# ir2104_V2_1.net
KiCad netlist of a schematic drawn in EasyEDA Pro
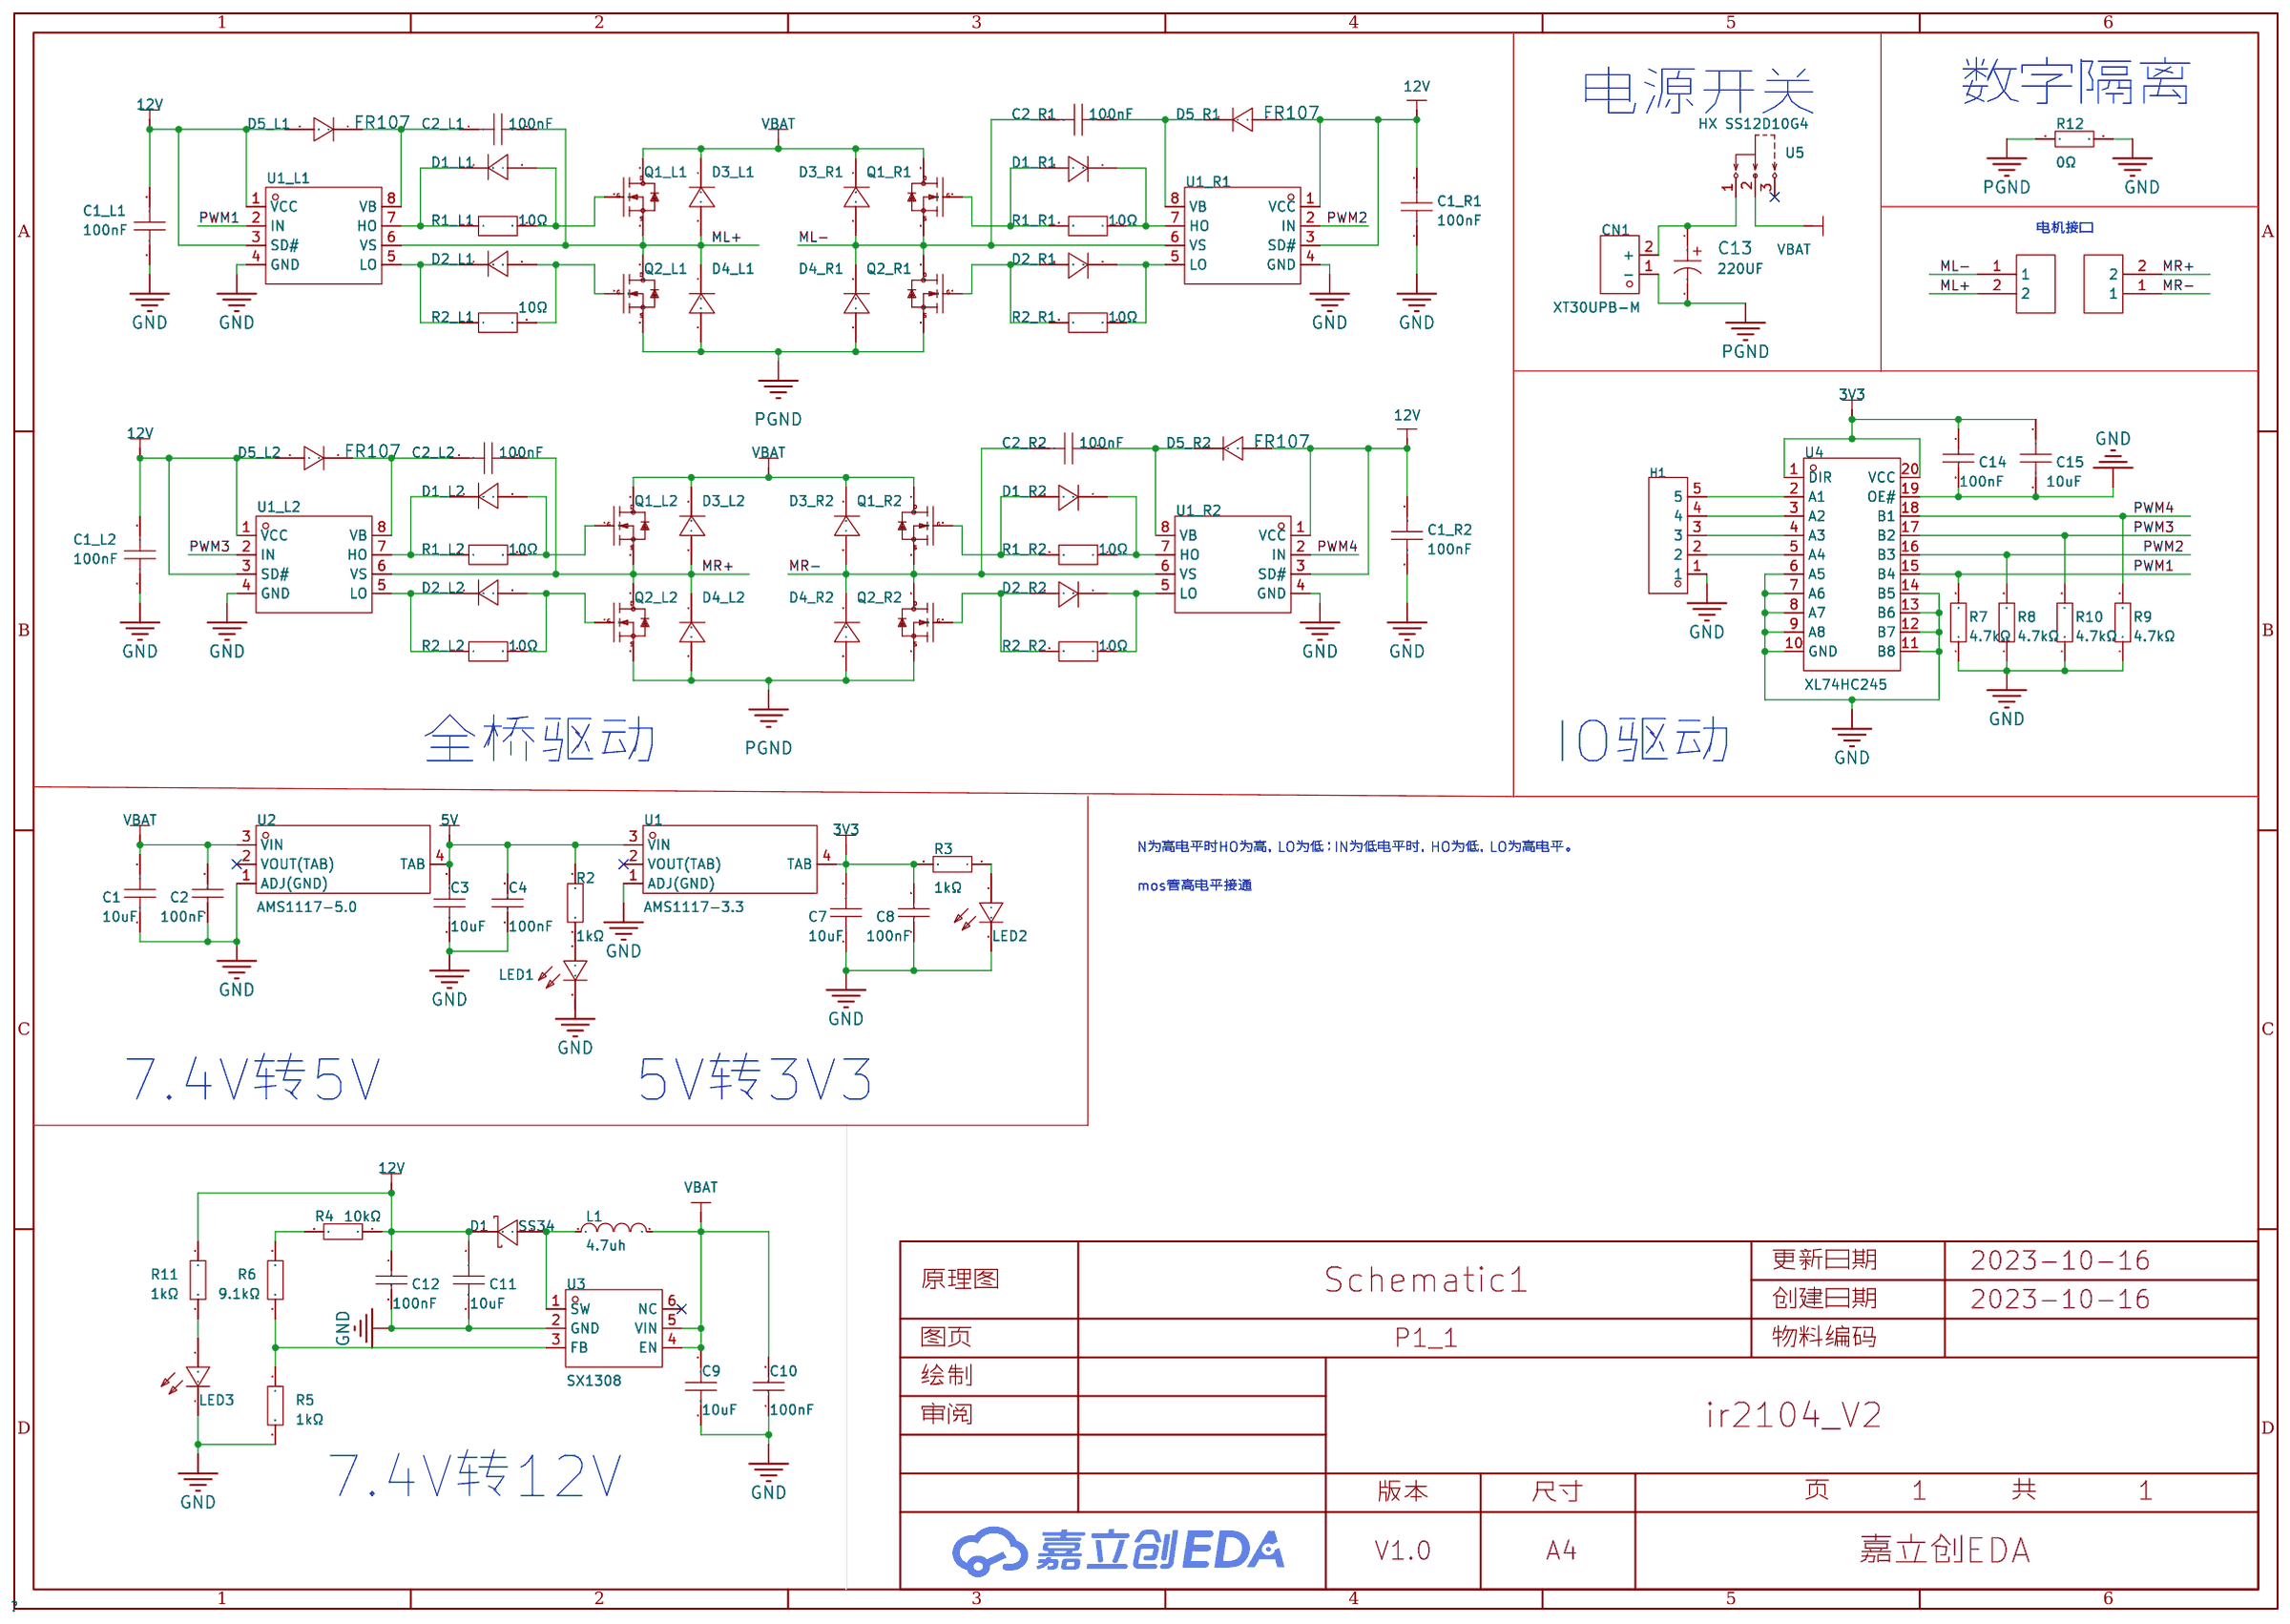
[diagram p0: schematic sheet]

(export (version "E")
  (design (tool "Eeschema 10.0.6"))
  (components
    (comp (ref "C1")
      (value "10uF")
      (footprint "easyedapro:C0603")
      (description "容值:10uF;精度:±20%;额定电压:25V;材质(温度系数):X5R;")
      (fields
        (field (name "Manufacturer Part") "CL10A106MA8NRNC")
        (field (name "Manufacturer") "SAMSUNG(三星)")
      )
      (libsource (lib "easyedapro") (part "CL10A106MA8NRNC"))
    )
    (comp (ref "C1_L1")
      (value "100nF")
      (footprint "easyedapro:C0603")
      (description "容值:100nF;精度:±10%;额定电压:50V;材质(温度系数):X7R;")
      (fields
        (field (name "Manufacturer Part") "CL10B104KB8NNNC")
        (field (name "Manufacturer") "SAMSUNG(三星)")
      )
      (libsource (lib "easyedapro") (part "CL10B104KB8NNNC"))
    )
    (comp (ref "C1_L2")
      (value "100nF")
      (footprint "easyedapro:C0603")
      (description "容值:100nF;精度:±10%;额定电压:50V;材质(温度系数):X7R;")
      (fields
        (field (name "Manufacturer Part") "CL10B104KB8NNNC")
        (field (name "Manufacturer") "SAMSUNG(三星)")
      )
      (libsource (lib "easyedapro") (part "CL10B104KB8NNNC"))
    )
    (comp (ref "C1_R1")
      (value "100nF")
      (footprint "easyedapro:C0603")
      (description "容值:100nF;精度:±10%;额定电压:50V;材质(温度系数):X7R;")
      (fields
        (field (name "Manufacturer Part") "CL10B104KB8NNNC")
        (field (name "Manufacturer") "SAMSUNG(三星)")
      )
      (libsource (lib "easyedapro") (part "CL10B104KB8NNNC"))
    )
    (comp (ref "C1_R2")
      (value "100nF")
      (footprint "easyedapro:C0603")
      (description "容值:100nF;精度:±10%;额定电压:50V;材质(温度系数):X7R;")
      (fields
        (field (name "Manufacturer Part") "CL10B104KB8NNNC")
        (field (name "Manufacturer") "SAMSUNG(三星)")
      )
      (libsource (lib "easyedapro") (part "CL10B104KB8NNNC"))
    )
    (comp (ref "C2")
      (value "100nF")
      (footprint "easyedapro:C0603")
      (description "容值:100nF;精度:±10%;额定电压:50V;材质(温度系数):X7R;")
      (fields (field (name "Manufacturer Part") "0603B104K500NT") (field (name "Manufacturer") "FH(风华)"))
      (libsource (lib "easyedapro") (part "0603B104K500NT"))
    )
    (comp (ref "C2_L1")
      (value "100nF")
      (footprint "easyedapro:C0603")
      (description "容值:100nF;精度:±10%;额定电压:50V;材质(温度系数):X7R;")
      (fields
        (field (name "Manufacturer Part") "CL10B104KB8NNNC")
        (field (name "Manufacturer") "SAMSUNG(三星)")
      )
      (libsource (lib "easyedapro") (part "CL10B104KB8NNNC"))
    )
    (comp (ref "C2_L2")
      (value "100nF")
      (footprint "easyedapro:C0603")
      (description "容值:100nF;精度:±10%;额定电压:50V;材质(温度系数):X7R;")
      (fields
        (field (name "Manufacturer Part") "CL10B104KB8NNNC")
        (field (name "Manufacturer") "SAMSUNG(三星)")
      )
      (libsource (lib "easyedapro") (part "CL10B104KB8NNNC"))
    )
    (comp (ref "C2_R1")
      (value "100nF")
      (footprint "easyedapro:C0603")
      (description "容值:100nF;精度:±10%;额定电压:50V;材质(温度系数):X7R;")
      (fields
        (field (name "Manufacturer Part") "CL10B104KB8NNNC")
        (field (name "Manufacturer") "SAMSUNG(三星)")
      )
      (libsource (lib "easyedapro") (part "CL10B104KB8NNNC"))
    )
    (comp (ref "C2_R2")
      (value "100nF")
      (footprint "easyedapro:C0603")
      (description "容值:100nF;精度:±10%;额定电压:50V;材质(温度系数):X7R;")
      (fields
        (field (name "Manufacturer Part") "CL10B104KB8NNNC")
        (field (name "Manufacturer") "SAMSUNG(三星)")
      )
      (libsource (lib "easyedapro") (part "CL10B104KB8NNNC"))
    )
    (comp (ref "C3")
      (value "10uF")
      (footprint "easyedapro:C0603")
      (description "容值:10uF;精度:±20%;额定电压:25V;材质(温度系数):X5R;")
      (fields
        (field (name "Manufacturer Part") "CL10A106MA8NRNC")
        (field (name "Manufacturer") "SAMSUNG(三星)")
      )
      (libsource (lib "easyedapro") (part "CL10A106MA8NRNC"))
    )
    (comp (ref "C4")
      (value "100nF")
      (footprint "easyedapro:C0603")
      (description "容值:100nF;精度:±10%;额定电压:50V;材质(温度系数):X7R;")
      (fields (field (name "Manufacturer Part") "0603B104K500NT") (field (name "Manufacturer") "FH(风华)"))
      (libsource (lib "easyedapro") (part "0603B104K500NT"))
    )
    (comp (ref "C7")
      (value "10uF")
      (footprint "easyedapro:C0603")
      (description "容值:10uF;精度:±20%;额定电压:25V;材质(温度系数):X5R;")
      (fields
        (field (name "Manufacturer Part") "CL10A106MA8NRNC")
        (field (name "Manufacturer") "SAMSUNG(三星)")
      )
      (libsource (lib "easyedapro") (part "CL10A106MA8NRNC"))
    )
    (comp (ref "C8")
      (value "100nF")
      (footprint "easyedapro:C0603")
      (description "容值:100nF;精度:±10%;额定电压:50V;材质(温度系数):X7R;")
      (fields (field (name "Manufacturer Part") "0603B104K500NT") (field (name "Manufacturer") "FH(风华)"))
      (libsource (lib "easyedapro") (part "0603B104K500NT"))
    )
    (comp (ref "C9")
      (value "10uF")
      (footprint "easyedapro:C0603")
      (description "容值:10uF;精度:±20%;额定电压:25V;材质(温度系数):X5R;")
      (fields
        (field (name "Manufacturer Part") "CL10A106MA8NRNC")
        (field (name "Manufacturer") "SAMSUNG(三星)")
      )
      (libsource (lib "easyedapro") (part "CL10A106MA8NRNC"))
    )
    (comp (ref "C10")
      (value "100nF")
      (footprint "easyedapro:C0603")
      (description "容值:100nF;精度:±10%;额定电压:50V;材质(温度系数):X7R;")
      (fields (field (name "Manufacturer Part") "0603B104K500NT") (field (name "Manufacturer") "FH(风华)"))
      (libsource (lib "easyedapro") (part "0603B104K500NT"))
    )
    (comp (ref "C11")
      (value "10uF")
      (footprint "easyedapro:C0603")
      (description "容值:10uF;精度:±20%;额定电压:25V;材质(温度系数):X5R;")
      (fields
        (field (name "Manufacturer Part") "CL10A106MA8NRNC")
        (field (name "Manufacturer") "SAMSUNG(三星)")
      )
      (libsource (lib "easyedapro") (part "CL10A106MA8NRNC"))
    )
    (comp (ref "C12")
      (value "100nF")
      (footprint "easyedapro:C0603")
      (description "容值:100nF;精度:±10%;额定电压:50V;材质(温度系数):X7R;")
      (fields (field (name "Manufacturer Part") "0603B104K500NT") (field (name "Manufacturer") "FH(风华)"))
      (libsource (lib "easyedapro") (part "0603B104K500NT"))
    )
    (comp (ref "C13")
      (value "220UF")
      (footprint "easyedapro:CAP-SMD_BD8.0-L8.3-W8.3-LS9.3-FD")
      (fields (field (name "Manufacturer") "KNSCHA(科尼盛)"))
      (libsource (lib "easyedapro") (part "FZ470UF16V90RV0148"))
    )
    (comp (ref "C14")
      (value "100nF")
      (footprint "easyedapro:C0603")
      (description "容值:100nF;精度:±10%;额定电压:50V;材质(温度系数):X7R;")
      (fields (field (name "Manufacturer Part") "0603B104K500NT") (field (name "Manufacturer") "FH(风华)"))
      (libsource (lib "easyedapro") (part "0603B104K500NT"))
    )
    (comp (ref "C15")
      (value "10uF")
      (footprint "easyedapro:C0603")
      (description "容值:10uF;精度:±20%;额定电压:25V;材质(温度系数):X5R;")
      (fields
        (field (name "Manufacturer Part") "CL10A106MA8NRNC")
        (field (name "Manufacturer") "SAMSUNG(三星)")
      )
      (libsource (lib "easyedapro") (part "CL10A106MA8NRNC"))
    )
    (comp (ref "CN1")
      (value "XT30UPB-M")
      (footprint "easyedapro:CONN-TH_XT30UPB-M")
      (fields (field (name "Manufacturer") "AMASS(艾迈斯)"))
      (libsource (lib "easyedapro") (part "XT30UPB-M"))
    )
    (comp (ref "D1")
      (value "SS34")
      (footprint "easyedapro:SMA_L4.3-W2.6-LS5.2-RD")
      (description "二极管配置:独立式;直流反向耐压(Vr):40V;平均整流电流(Io):3A;正向压降(Vf):550mV@3A;")
      (fields (field (name "Manufacturer") "MDD"))
      (libsource (lib "easyedapro") (part "SS34_C8678"))
    )
    (comp (ref "D1_L1")
      (value "US1M")
      (footprint "easyedapro:SMA_L4.4-W2.8-LS5.4-RD")
      (fields (field (name "Manufacturer") "MDD"))
      (libsource (lib "easyedapro") (part "US1MG_C412437"))
    )
    (comp (ref "D1_L2")
      (value "US1M")
      (footprint "easyedapro:SMA_L4.4-W2.8-LS5.4-RD")
      (fields (field (name "Manufacturer") "MDD"))
      (libsource (lib "easyedapro") (part "US1MG_C412437"))
    )
    (comp (ref "D1_R1")
      (value "US1M")
      (footprint "easyedapro:SMA_L4.4-W2.8-LS5.4-RD")
      (fields (field (name "Manufacturer") "MDD"))
      (libsource (lib "easyedapro") (part "US1MG_C412437"))
    )
    (comp (ref "D1_R2")
      (value "US1M")
      (footprint "easyedapro:SMA_L4.4-W2.8-LS5.4-RD")
      (fields (field (name "Manufacturer") "MDD"))
      (libsource (lib "easyedapro") (part "US1MG_C412437"))
    )
    (comp (ref "D2_L1")
      (value "US1M")
      (footprint "easyedapro:SMA_L4.4-W2.8-LS5.4-RD")
      (fields (field (name "Manufacturer") "MDD"))
      (libsource (lib "easyedapro") (part "US1MG_C412437"))
    )
    (comp (ref "D2_L2")
      (value "US1M")
      (footprint "easyedapro:SMA_L4.4-W2.8-LS5.4-RD")
      (fields (field (name "Manufacturer") "MDD"))
      (libsource (lib "easyedapro") (part "US1MG_C412437"))
    )
    (comp (ref "D2_R1")
      (value "US1M")
      (footprint "easyedapro:SMA_L4.4-W2.8-LS5.4-RD")
      (fields (field (name "Manufacturer") "MDD"))
      (libsource (lib "easyedapro") (part "US1MG_C412437"))
    )
    (comp (ref "D2_R2")
      (value "US1M")
      (footprint "easyedapro:SMA_L4.4-W2.8-LS5.4-RD")
      (fields (field (name "Manufacturer") "MDD"))
      (libsource (lib "easyedapro") (part "US1MG_C412437"))
    )
    (comp (ref "D3_L1")
      (value "US1M")
      (footprint "easyedapro:SMA_L4.4-W2.8-LS5.4-RD")
      (fields (field (name "Manufacturer") "MDD"))
      (libsource (lib "easyedapro") (part "US1MG_C412437"))
    )
    (comp (ref "D3_L2")
      (value "US1M")
      (footprint "easyedapro:SMA_L4.4-W2.8-LS5.4-RD")
      (fields (field (name "Manufacturer") "MDD"))
      (libsource (lib "easyedapro") (part "US1MG_C412437"))
    )
    (comp (ref "D3_R1")
      (value "US1M")
      (footprint "easyedapro:SMA_L4.4-W2.8-LS5.4-RD")
      (fields (field (name "Manufacturer") "MDD"))
      (libsource (lib "easyedapro") (part "US1MG_C412437"))
    )
    (comp (ref "D3_R2")
      (value "US1M")
      (footprint "easyedapro:SMA_L4.4-W2.8-LS5.4-RD")
      (fields (field (name "Manufacturer") "MDD"))
      (libsource (lib "easyedapro") (part "US1MG_C412437"))
    )
    (comp (ref "D4_L1")
      (value "US1M")
      (footprint "easyedapro:SMA_L4.4-W2.8-LS5.4-RD")
      (fields (field (name "Manufacturer") "MDD"))
      (libsource (lib "easyedapro") (part "US1MG_C412437"))
    )
    (comp (ref "D4_L2")
      (value "US1M")
      (footprint "easyedapro:SMA_L4.4-W2.8-LS5.4-RD")
      (fields (field (name "Manufacturer") "MDD"))
      (libsource (lib "easyedapro") (part "US1MG_C412437"))
    )
    (comp (ref "D4_R1")
      (value "US1M")
      (footprint "easyedapro:SMA_L4.4-W2.8-LS5.4-RD")
      (fields (field (name "Manufacturer") "MDD"))
      (libsource (lib "easyedapro") (part "US1MG_C412437"))
    )
    (comp (ref "D4_R2")
      (value "US1M")
      (footprint "easyedapro:SMA_L4.4-W2.8-LS5.4-RD")
      (fields (field (name "Manufacturer") "MDD"))
      (libsource (lib "easyedapro") (part "US1MG_C412437"))
    )
    (comp (ref "D5_L1")
      (value "FR107")
      (footprint "easyedapro:SOD-123_L2.8-W1.8-LS3.7-RD")
      (fields (field (name "Manufacturer") "BORN(伯恩半导体)"))
      (libsource (lib "easyedapro") (part "FR107_C511885"))
    )
    (comp (ref "D5_L2")
      (value "FR107")
      (footprint "easyedapro:SOD-123_L2.8-W1.8-LS3.7-RD")
      (fields (field (name "Manufacturer") "BORN(伯恩半导体)"))
      (libsource (lib "easyedapro") (part "FR107_C511885"))
    )
    (comp (ref "D5_R1")
      (value "FR107")
      (footprint "easyedapro:SOD-123_L2.8-W1.8-LS3.7-RD")
      (fields (field (name "Manufacturer") "BORN(伯恩半导体)"))
      (libsource (lib "easyedapro") (part "FR107_C511885"))
    )
    (comp (ref "D5_R2")
      (value "FR107")
      (footprint "easyedapro:SOD-123_L2.8-W1.8-LS3.7-RD")
      (fields (field (name "Manufacturer") "BORN(伯恩半导体)"))
      (libsource (lib "easyedapro") (part "FR107_C511885"))
    )
    (comp (ref "H1")
      (value "PZ254V-11-05P")
      (footprint "easyedapro:HDR-TH_5P-P2.54-V-M")
      (fields (field (name "Manufacturer") "XFCN(兴飞)"))
      (libsource (lib "easyedapro") (part "PZ254V-11-05P"))
    )
    (comp (ref "L1")
      (value "4.7uh")
      (footprint "easyedapro:IND-SMD_L7.3-W6.6")
      (description "电感值:10uH;精度:±20%;额定电流:-;")
      (fields (field (name "Manufacturer Part") "SMMS0630-100M") (field (name "Manufacturer") "SXN(顺翔诺)"))
      (libsource (lib "easyedapro") (part "SMMS0630-100M"))
    )
    (comp (ref "LED1")
      (value "NCD0603R1")
      (footprint "easyedapro:LED0603-RD_RED")
      (description "发光颜色:红灯;")
      (fields (field (name "Manufacturer") "国星光电"))
      (libsource (lib "easyedapro") (part "FC-DA1608HRK-620D"))
    )
    (comp (ref "LED2")
      (value "NCD0603R1")
      (footprint "easyedapro:LED0603-RD_RED")
      (description "发光颜色:红灯;")
      (fields (field (name "Manufacturer") "国星光电"))
      (libsource (lib "easyedapro") (part "FC-DA1608HRK-620D"))
    )
    (comp (ref "LED3")
      (value "NCD0603R1")
      (footprint "easyedapro:LED0603-RD_RED")
      (description "发光颜色:红灯;")
      (fields (field (name "Manufacturer") "国星光电"))
      (libsource (lib "easyedapro") (part "FC-DA1608HRK-620D"))
    )
    (comp (ref "P1")
      (value "WJ500V-5.08-2P")
      (footprint "easyedapro:CONN-TH_2P-P5.00_WJ500V-5.08-2P")
      (fields (field (name "Manufacturer") "KANGNEX(康奈克斯电气)"))
      (libsource (lib "easyedapro") (part "WJ500V-5.08-2P-14-00A"))
    )
    (comp (ref "P2")
      (value "WJ500V-5.08-2P")
      (footprint "easyedapro:CONN-TH_2P-P5.00_WJ500V-5.08-2P")
      (fields (field (name "Manufacturer") "KANGNEX(康奈克斯电气)"))
      (libsource (lib "easyedapro") (part "WJ500V-5.08-2P-14-00A"))
    )
    (comp (ref "Q1_L1")
      (value "IRFR3607TRPBF")
      (footprint "easyedapro:TO-252-3_L6.5-W5.8-P4.58-BL")
      (fields (field (name "Manufacturer") "Infineon(英飞凌)"))
      (libsource (lib "easyedapro") (part "IRFR3607TRPBF"))
    )
    (comp (ref "Q1_L2")
      (value "IRFR3607TRPBF")
      (footprint "easyedapro:TO-252-3_L6.5-W5.8-P4.58-BL")
      (fields (field (name "Manufacturer") "Infineon(英飞凌)"))
      (libsource (lib "easyedapro") (part "IRFR3607TRPBF"))
    )
    (comp (ref "Q1_R1")
      (value "IRFR3607TRPBF")
      (footprint "easyedapro:TO-252-3_L6.5-W5.8-P4.58-BL")
      (fields (field (name "Manufacturer") "Infineon(英飞凌)"))
      (libsource (lib "easyedapro") (part "IRFR3607TRPBF"))
    )
    (comp (ref "Q1_R2")
      (value "IRFR3607TRPBF")
      (footprint "easyedapro:TO-252-3_L6.5-W5.8-P4.58-BL")
      (fields (field (name "Manufacturer") "Infineon(英飞凌)"))
      (libsource (lib "easyedapro") (part "IRFR3607TRPBF"))
    )
    (comp (ref "Q2_L1")
      (value "IRFR3607TRPBF")
      (footprint "easyedapro:TO-252-3_L6.5-W5.8-P4.58-BL")
      (fields (field (name "Manufacturer") "Infineon(英飞凌)"))
      (libsource (lib "easyedapro") (part "IRFR3607TRPBF"))
    )
    (comp (ref "Q2_L2")
      (value "IRFR3607TRPBF")
      (footprint "easyedapro:TO-252-3_L6.5-W5.8-P4.58-BL")
      (fields (field (name "Manufacturer") "Infineon(英飞凌)"))
      (libsource (lib "easyedapro") (part "IRFR3607TRPBF"))
    )
    (comp (ref "Q2_R1")
      (value "IRFR3607TRPBF")
      (footprint "easyedapro:TO-252-3_L6.5-W5.8-P4.58-BL")
      (fields (field (name "Manufacturer") "Infineon(英飞凌)"))
      (libsource (lib "easyedapro") (part "IRFR3607TRPBF"))
    )
    (comp (ref "Q2_R2")
      (value "IRFR3607TRPBF")
      (footprint "easyedapro:TO-252-3_L6.5-W5.8-P4.58-BL")
      (fields (field (name "Manufacturer") "Infineon(英飞凌)"))
      (libsource (lib "easyedapro") (part "IRFR3607TRPBF"))
    )
    (comp (ref "R1_L1")
      (value "10Ω")
      (footprint "easyedapro:R0603")
      (description "阻值:10Ω;精度:±0.5%;功率:250mW;")
      (fields (field (name "Manufacturer Part") "ERJUP3D10R0V") (field (name "Manufacturer") "PANASONIC(松下)"))
      (libsource (lib "easyedapro") (part "ERJUP3D10R0V"))
    )
    (comp (ref "R1_L2")
      (value "10Ω")
      (footprint "easyedapro:R0603")
      (description "阻值:10Ω;精度:±0.5%;功率:250mW;")
      (fields (field (name "Manufacturer Part") "ERJUP3D10R0V") (field (name "Manufacturer") "PANASONIC(松下)"))
      (libsource (lib "easyedapro") (part "ERJUP3D10R0V"))
    )
    (comp (ref "R1_R1")
      (value "10Ω")
      (footprint "easyedapro:R0603")
      (description "阻值:10Ω;精度:±0.5%;功率:250mW;")
      (fields (field (name "Manufacturer Part") "ERJUP3D10R0V") (field (name "Manufacturer") "PANASONIC(松下)"))
      (libsource (lib "easyedapro") (part "ERJUP3D10R0V"))
    )
    (comp (ref "R1_R2")
      (value "10Ω")
      (footprint "easyedapro:R0603")
      (description "阻值:10Ω;精度:±0.5%;功率:250mW;")
      (fields (field (name "Manufacturer Part") "ERJUP3D10R0V") (field (name "Manufacturer") "PANASONIC(松下)"))
      (libsource (lib "easyedapro") (part "ERJUP3D10R0V"))
    )
    (comp (ref "R2")
      (value "1kΩ")
      (footprint "easyedapro:R0603")
      (description "电阻类型:厚膜电阻;阻值:1kΩ;精度:±1%;功率:100mW;")
      (fields
        (field (name "Manufacturer Part") "0603WAF1001T5E")
        (field (name "Manufacturer") "UNI-ROYAL(厚声)")
      )
      (libsource (lib "easyedapro") (part "0603WAF1001T5E"))
    )
    (comp (ref "R2_L1")
      (value "10Ω")
      (footprint "easyedapro:R0603")
      (description "阻值:10Ω;精度:±0.5%;功率:250mW;")
      (fields (field (name "Manufacturer Part") "ERJUP3D10R0V") (field (name "Manufacturer") "PANASONIC(松下)"))
      (libsource (lib "easyedapro") (part "ERJUP3D10R0V"))
    )
    (comp (ref "R2_L2")
      (value "10Ω")
      (footprint "easyedapro:R0603")
      (description "阻值:10Ω;精度:±0.5%;功率:250mW;")
      (fields (field (name "Manufacturer Part") "ERJUP3D10R0V") (field (name "Manufacturer") "PANASONIC(松下)"))
      (libsource (lib "easyedapro") (part "ERJUP3D10R0V"))
    )
    (comp (ref "R2_R1")
      (value "10Ω")
      (footprint "easyedapro:R0603")
      (description "阻值:10Ω;精度:±0.5%;功率:250mW;")
      (fields (field (name "Manufacturer Part") "ERJUP3D10R0V") (field (name "Manufacturer") "PANASONIC(松下)"))
      (libsource (lib "easyedapro") (part "ERJUP3D10R0V"))
    )
    (comp (ref "R2_R2")
      (value "10Ω")
      (footprint "easyedapro:R0603")
      (description "阻值:10Ω;精度:±0.5%;功率:250mW;")
      (fields (field (name "Manufacturer Part") "ERJUP3D10R0V") (field (name "Manufacturer") "PANASONIC(松下)"))
      (libsource (lib "easyedapro") (part "ERJUP3D10R0V"))
    )
    (comp (ref "R3")
      (value "1kΩ")
      (footprint "easyedapro:R0603")
      (description "电阻类型:厚膜电阻;阻值:1kΩ;精度:±1%;功率:100mW;")
      (fields
        (field (name "Manufacturer Part") "0603WAF1001T5E")
        (field (name "Manufacturer") "UNI-ROYAL(厚声)")
      )
      (libsource (lib "easyedapro") (part "0603WAF1001T5E"))
    )
    (comp (ref "R4")
      (value "10kΩ")
      (footprint "easyedapro:R0603")
      (description "电阻类型:薄膜电阻;阻值:10kΩ;精度:±0.1%;功率:100mW;")
      (fields (field (name "Manufacturer Part") "RT0603BRD0710KL") (field (name "Manufacturer") "YAGEO(国巨)"))
      (libsource (lib "easyedapro") (part "RT0603BRD0710KL"))
    )
    (comp (ref "R5")
      (value "1kΩ")
      (footprint "easyedapro:R0603")
      (description "电阻类型:薄膜电阻;阻值:1kΩ;精度:±0.1%;功率:100mW;")
      (fields (field (name "Manufacturer Part") "RT0603BRD071KL") (field (name "Manufacturer") "YAGEO(国巨)"))
      (libsource (lib "easyedapro") (part "RT0603BRD071KL"))
    )
    (comp (ref "R6")
      (value "9.1kΩ")
      (footprint "easyedapro:R0603")
      (description "电阻类型:薄膜电阻;阻值:9.1kΩ;精度:±0.1%;功率:100mW;")
      (fields (field (name "Manufacturer Part") "PTFR0603B9K10P9") (field (name "Manufacturer") "RESI(开步睿思）"))
      (libsource (lib "easyedapro") (part "PTFR0603B9K10P9"))
    )
    (comp (ref "R7")
      (value "4.7kΩ")
      (footprint "easyedapro:R0603")
      (description "电阻类型:厚膜电阻;阻值:4.7kΩ;精度:±1%;功率:100mW;")
      (fields
        (field (name "Manufacturer Part") "0603WAF4701T5E")
        (field (name "Manufacturer") "UNI-ROYAL(厚声)")
      )
      (libsource (lib "easyedapro") (part "0603WAF4701T5E"))
    )
    (comp (ref "R8")
      (value "4.7kΩ")
      (footprint "easyedapro:R0603")
      (description "电阻类型:厚膜电阻;阻值:4.7kΩ;精度:±1%;功率:100mW;")
      (fields
        (field (name "Manufacturer Part") "0603WAF4701T5E")
        (field (name "Manufacturer") "UNI-ROYAL(厚声)")
      )
      (libsource (lib "easyedapro") (part "0603WAF4701T5E"))
    )
    (comp (ref "R9")
      (value "4.7kΩ")
      (footprint "easyedapro:R0603")
      (description "电阻类型:厚膜电阻;阻值:4.7kΩ;精度:±1%;功率:100mW;")
      (fields
        (field (name "Manufacturer Part") "0603WAF4701T5E")
        (field (name "Manufacturer") "UNI-ROYAL(厚声)")
      )
      (libsource (lib "easyedapro") (part "0603WAF4701T5E"))
    )
    (comp (ref "R10")
      (value "4.7kΩ")
      (footprint "easyedapro:R0603")
      (description "电阻类型:厚膜电阻;阻值:4.7kΩ;精度:±1%;功率:100mW;")
      (fields
        (field (name "Manufacturer Part") "0603WAF4701T5E")
        (field (name "Manufacturer") "UNI-ROYAL(厚声)")
      )
      (libsource (lib "easyedapro") (part "0603WAF4701T5E"))
    )
    (comp (ref "R11")
      (value "1kΩ")
      (footprint "easyedapro:R0603")
      (description "电阻类型:厚膜电阻;阻值:1kΩ;精度:±1%;功率:100mW;")
      (fields
        (field (name "Manufacturer Part") "0603WAF1001T5E")
        (field (name "Manufacturer") "UNI-ROYAL(厚声)")
      )
      (libsource (lib "easyedapro") (part "0603WAF1001T5E"))
    )
    (comp (ref "R12")
      (value "0Ω")
      (footprint "easyedapro:R0805")
      (description "电阻类型:厚膜电阻;阻值:0Ω;精度:±1%;功率:125mW;")
      (fields
        (field (name "Manufacturer Part") "0805W8F0000T5E")
        (field (name "Manufacturer") "UNI-ROYAL(厚声)")
      )
      (libsource (lib "easyedapro") (part "0805W8F0000T5E"))
    )
    (comp (ref "U1")
      (value "AMS1117-3.3")
      (footprint "easyedapro:SOT-223-4_L6.5-W3.5-P2.30-LS7.0-BR")
      (description "输出类型:固定;输出极性:正;最大输入电压:18V;输出电压:3.3V;输出电流:1A;电源纹波抑制比(PSRR):60dB@(120Hz);")
      (fields (field (name "Manufacturer") "UMW(广东友台半导体)"))
      (libsource (lib "easyedapro") (part "AMS1117-3.3_C347222"))
    )
    (comp (ref "U1_L1")
      (value "EG2104")
      (footprint "easyedapro:SOP-8_L5.0-W4.0-P1.27-LS6.2-BL")
      (description "高性价比, 600V，半桥式Nmos预驱动器")
      (fields (field (name "Manufacturer") "EG(屹晶微)"))
      (libsource (lib "easyedapro") (part "EG2104"))
    )
    (comp (ref "U1_L2")
      (value "EG2104")
      (footprint "easyedapro:SOP-8_L5.0-W4.0-P1.27-LS6.2-BL")
      (description "高性价比, 600V，半桥式Nmos预驱动器")
      (fields (field (name "Manufacturer") "EG(屹晶微)"))
      (libsource (lib "easyedapro") (part "EG2104"))
    )
    (comp (ref "U1_R1")
      (value "EG2104")
      (footprint "easyedapro:SOP-8_L5.0-W4.0-P1.27-LS6.2-BL")
      (description "高性价比, 600V，半桥式Nmos预驱动器")
      (fields (field (name "Manufacturer") "EG(屹晶微)"))
      (libsource (lib "easyedapro") (part "EG2104"))
    )
    (comp (ref "U1_R2")
      (value "EG2104")
      (footprint "easyedapro:SOP-8_L5.0-W4.0-P1.27-LS6.2-BL")
      (description "高性价比, 600V，半桥式Nmos预驱动器")
      (fields (field (name "Manufacturer") "EG(屹晶微)"))
      (libsource (lib "easyedapro") (part "EG2104"))
    )
    (comp (ref "U2")
      (value "AMS1117-5.0")
      (footprint "easyedapro:SOT-223_L6.7-W3.5-P2.30-BR")
      (description "输出类型:固定;输出极性:正;最大输入电压:18V;输出电压:5V;输出电流:1A;电源纹波抑制比(PSRR):60dB@(120Hz);")
      (fields (field (name "Manufacturer") "UMW(广东友台半导体)"))
      (libsource (lib "easyedapro") (part "AMS1117-5.0_C347223"))
    )
    (comp (ref "U3")
      (value "SX1308")
      (footprint "easyedapro:SOT-23-6_L2.9-W1.6-P0.95-LS2.8-BL")
      (description "功能类型:升压型;同步整流:否;输出通道数:1;拓扑结构:升压式;输入电压:2V~24V;输出电压:28V;输出电流(最大值):-;开关频率:1.2MHz;")
      (fields (field (name "Manufacturer") "SX(硕芯科技)"))
      (libsource (lib "easyedapro") (part "SX1308"))
    )
    (comp (ref "U4")
      (value "XL74HC245")
      (footprint "easyedapro:SOP-20_L12.8-W7.5-P1.27-LS10.4-BL")
      (description "八路总线收发器")
      (fields (field (name "Manufacturer") "XINLUDA(信路达)"))
      (libsource (lib "easyedapro") (part "XL74HC245"))
    )
    (comp (ref "U5")
      (value "HX SS12D10G4")
      (footprint "easyedapro:SW-TH_SHOU-HAN_SS12D10G4")
      (fields (field (name "Manufacturer") "hanxia(韩下)"))
      (libsource (lib "easyedapro") (part "HX SS12D10G4"))
    )
  )
  (nets
    (net (code "1") (name "/ML+") (class "Default")
      (node (ref "C2_L1") (pin "2") (pinfunction "2_2") (pintype "input"))
      (node (ref "D3_L1") (pin "2") (pinfunction "A_2") (pintype "input"))
      (node (ref "D4_L1") (pin "1") (pinfunction "C_1") (pintype "input"))
      (node (ref "P1") (pin "2") (pinfunction "2_2") (pintype "input"))
      (node (ref "Q1_L1") (pin "3") (pinfunction "S_3") (pintype "input"))
      (node (ref "Q2_L1") (pin "2") (pinfunction "D_2") (pintype "input"))
      (node (ref "U1_L1") (pin "6") (pinfunction "VS_6") (pintype "input"))
    )
    (net (code "2") (name "/ML-") (class "Default")
      (node (ref "C2_R1") (pin "2") (pinfunction "2_2") (pintype "input"))
      (node (ref "D3_R1") (pin "2") (pinfunction "A_2") (pintype "input"))
      (node (ref "D4_R1") (pin "1") (pinfunction "C_1") (pintype "input"))
      (node (ref "P1") (pin "1") (pinfunction "1_1") (pintype "input"))
      (node (ref "Q1_R1") (pin "3") (pinfunction "S_3") (pintype "input"))
      (node (ref "Q2_R1") (pin "2") (pinfunction "D_2") (pintype "input"))
      (node (ref "U1_R1") (pin "6") (pinfunction "VS_6") (pintype "input"))
    )
    (net (code "3") (name "/MR+") (class "Default")
      (node (ref "C2_L2") (pin "2") (pinfunction "2_2") (pintype "input"))
      (node (ref "D3_L2") (pin "2") (pinfunction "A_2") (pintype "input"))
      (node (ref "D4_L2") (pin "1") (pinfunction "C_1") (pintype "input"))
      (node (ref "P2") (pin "2") (pinfunction "2_2") (pintype "input"))
      (node (ref "Q1_L2") (pin "3") (pinfunction "S_3") (pintype "input"))
      (node (ref "Q2_L2") (pin "2") (pinfunction "D_2") (pintype "input"))
      (node (ref "U1_L2") (pin "6") (pinfunction "VS_6") (pintype "input"))
    )
    (net (code "4") (name "/MR-") (class "Default")
      (node (ref "C2_R2") (pin "2") (pinfunction "2_2") (pintype "input"))
      (node (ref "D3_R2") (pin "2") (pinfunction "A_2") (pintype "input"))
      (node (ref "D4_R2") (pin "1") (pinfunction "C_1") (pintype "input"))
      (node (ref "P2") (pin "1") (pinfunction "1_1") (pintype "input"))
      (node (ref "Q1_R2") (pin "3") (pinfunction "S_3") (pintype "input"))
      (node (ref "Q2_R2") (pin "2") (pinfunction "D_2") (pintype "input"))
      (node (ref "U1_R2") (pin "6") (pinfunction "VS_6") (pintype "input"))
    )
    (net (code "5") (name "/PWM1") (class "Default")
      (node (ref "R7") (pin "2") (pinfunction "2_2") (pintype "input"))
      (node (ref "U1_L1") (pin "2") (pinfunction "IN_2") (pintype "input"))
      (node (ref "U4") (pin "15") (pinfunction "B4_15") (pintype "input"))
    )
    (net (code "6") (name "/PWM2") (class "Default")
      (node (ref "R8") (pin "2") (pinfunction "2_2") (pintype "input"))
      (node (ref "U1_R1") (pin "2") (pinfunction "IN_2") (pintype "input"))
      (node (ref "U4") (pin "16") (pinfunction "B3_16") (pintype "input"))
    )
    (net (code "7") (name "/PWM3") (class "Default")
      (node (ref "R10") (pin "2") (pinfunction "2_2") (pintype "input"))
      (node (ref "U1_L2") (pin "2") (pinfunction "IN_2") (pintype "input"))
      (node (ref "U4") (pin "17") (pinfunction "B2_17") (pintype "input"))
    )
    (net (code "8") (name "/PWM4") (class "Default")
      (node (ref "R9") (pin "2") (pinfunction "2_2") (pintype "input"))
      (node (ref "U1_R2") (pin "2") (pinfunction "IN_2") (pintype "input"))
      (node (ref "U4") (pin "18") (pinfunction "B1_18") (pintype "input"))
    )
    (net (code "9") (name "3V3") (class "Default")
      (node (ref "C14") (pin "1") (pinfunction "1_1") (pintype "input"))
      (node (ref "C15") (pin "1") (pinfunction "1_1") (pintype "input"))
      (node (ref "C7") (pin "2") (pinfunction "2_2") (pintype "input"))
      (node (ref "C8") (pin "2") (pinfunction "2_2") (pintype "input"))
      (node (ref "R3") (pin "2") (pinfunction "2_2") (pintype "input"))
      (node (ref "U1") (pin "4") (pinfunction "TAB_4") (pintype "input"))
      (node (ref "U4") (pin "1") (pinfunction "DIR_1") (pintype "input"))
      (node (ref "U4") (pin "20") (pinfunction "VCC_20") (pintype "input"))
    )
    (net (code "10") (name "5V") (class "Default")
      (node (ref "C3") (pin "2") (pinfunction "2_2") (pintype "input"))
      (node (ref "C4") (pin "2") (pinfunction "2_2") (pintype "input"))
      (node (ref "R2") (pin "1") (pinfunction "1_1") (pintype "input"))
      (node (ref "U1") (pin "3") (pinfunction "VIN_3") (pintype "input"))
      (node (ref "U2") (pin "4") (pinfunction "TAB_4") (pintype "input"))
    )
    (net (code "11") (name "12V") (class "Default")
      (node (ref "C11") (pin "1") (pinfunction "1_1") (pintype "input"))
      (node (ref "C12") (pin "1") (pinfunction "1_1") (pintype "input"))
      (node (ref "C1_L1") (pin "2") (pinfunction "2_2") (pintype "input"))
      (node (ref "C1_L2") (pin "2") (pinfunction "2_2") (pintype "input"))
      (node (ref "C1_R1") (pin "2") (pinfunction "2_2") (pintype "input"))
      (node (ref "C1_R2") (pin "2") (pinfunction "2_2") (pintype "input"))
      (node (ref "D1") (pin "1") (pinfunction "K_1") (pintype "input"))
      (node (ref "D5_L1") (pin "2") (pinfunction "A_2") (pintype "input"))
      (node (ref "D5_L2") (pin "2") (pinfunction "A_2") (pintype "input"))
      (node (ref "D5_R1") (pin "2") (pinfunction "A_2") (pintype "input"))
      (node (ref "D5_R2") (pin "2") (pinfunction "A_2") (pintype "input"))
      (node (ref "R11") (pin "1") (pinfunction "1_1") (pintype "input"))
      (node (ref "R4") (pin "1") (pinfunction "1_1") (pintype "input"))
      (node (ref "U1_L1") (pin "1") (pinfunction "VCC_1") (pintype "input"))
      (node (ref "U1_L1") (pin "3") (pinfunction "SD#_3") (pintype "input"))
      (node (ref "U1_L2") (pin "1") (pinfunction "VCC_1") (pintype "input"))
      (node (ref "U1_L2") (pin "3") (pinfunction "SD#_3") (pintype "input"))
      (node (ref "U1_R1") (pin "1") (pinfunction "VCC_1") (pintype "input"))
      (node (ref "U1_R1") (pin "3") (pinfunction "SD#_3") (pintype "input"))
      (node (ref "U1_R2") (pin "1") (pinfunction "VCC_1") (pintype "input"))
      (node (ref "U1_R2") (pin "3") (pinfunction "SD#_3") (pintype "input"))
    )
    (net (code "12") (name "GND") (class "Default")
      (node (ref "C1") (pin "1") (pinfunction "1_1") (pintype "input"))
      (node (ref "C10") (pin "1") (pinfunction "1_1") (pintype "input"))
      (node (ref "C11") (pin "2") (pinfunction "2_2") (pintype "input"))
      (node (ref "C12") (pin "2") (pinfunction "2_2") (pintype "input"))
      (node (ref "C14") (pin "2") (pinfunction "2_2") (pintype "input"))
      (node (ref "C15") (pin "2") (pinfunction "2_2") (pintype "input"))
      (node (ref "C1_L1") (pin "1") (pinfunction "1_1") (pintype "input"))
      (node (ref "C1_L2") (pin "1") (pinfunction "1_1") (pintype "input"))
      (node (ref "C1_R1") (pin "1") (pinfunction "1_1") (pintype "input"))
      (node (ref "C1_R2") (pin "1") (pinfunction "1_1") (pintype "input"))
      (node (ref "C2") (pin "1") (pinfunction "1_1") (pintype "input"))
      (node (ref "C3") (pin "1") (pinfunction "1_1") (pintype "input"))
      (node (ref "C4") (pin "1") (pinfunction "1_1") (pintype "input"))
      (node (ref "C7") (pin "1") (pinfunction "1_1") (pintype "input"))
      (node (ref "C8") (pin "1") (pinfunction "1_1") (pintype "input"))
      (node (ref "C9") (pin "1") (pinfunction "1_1") (pintype "input"))
      (node (ref "H1") (pin "1") (pinfunction "1_1") (pintype "input"))
      (node (ref "LED1") (pin "1") (pinfunction "K_1") (pintype "input"))
      (node (ref "LED2") (pin "1") (pinfunction "K_1") (pintype "input"))
      (node (ref "LED3") (pin "1") (pinfunction "K_1") (pintype "input"))
      (node (ref "R10") (pin "1") (pinfunction "1_1") (pintype "input"))
      (node (ref "R12") (pin "2") (pinfunction "2_2") (pintype "input"))
      (node (ref "R5") (pin "2") (pinfunction "2_2") (pintype "input"))
      (node (ref "R7") (pin "1") (pinfunction "1_1") (pintype "input"))
      (node (ref "R8") (pin "1") (pinfunction "1_1") (pintype "input"))
      (node (ref "R9") (pin "1") (pinfunction "1_1") (pintype "input"))
      (node (ref "U1") (pin "1") (pinfunction "ADJ(GND)_1") (pintype "input"))
      (node (ref "U1_L1") (pin "4") (pinfunction "GND_4") (pintype "input"))
      (node (ref "U1_L2") (pin "4") (pinfunction "GND_4") (pintype "input"))
      (node (ref "U1_R1") (pin "4") (pinfunction "GND_4") (pintype "input"))
      (node (ref "U1_R2") (pin "4") (pinfunction "GND_4") (pintype "input"))
      (node (ref "U2") (pin "1") (pinfunction "ADJ(GND)_1") (pintype "input"))
      (node (ref "U3") (pin "2") (pinfunction "GND_2") (pintype "input"))
      (node (ref "U4") (pin "10") (pinfunction "GND_10") (pintype "input"))
      (node (ref "U4") (pin "11") (pinfunction "B8_11") (pintype "input"))
      (node (ref "U4") (pin "12") (pinfunction "B7_12") (pintype "input"))
      (node (ref "U4") (pin "13") (pinfunction "B6_13") (pintype "input"))
      (node (ref "U4") (pin "14") (pinfunction "B5_14") (pintype "input"))
      (node (ref "U4") (pin "19") (pinfunction "OE#_19") (pintype "input"))
      (node (ref "U4") (pin "6") (pinfunction "A5_6") (pintype "input"))
      (node (ref "U4") (pin "7") (pinfunction "A6_7") (pintype "input"))
      (node (ref "U4") (pin "8") (pinfunction "A7_8") (pintype "input"))
      (node (ref "U4") (pin "9") (pinfunction "A8_9") (pintype "input"))
    )
    (net (code "13") (name "Net-(CN1-+)") (class "Default")
      (node (ref "C13") (pin "1") (pinfunction "1_1") (pintype "input"))
      (node (ref "CN1") (pin "2") (pinfunction "+_2") (pintype "input"))
      (node (ref "U5") (pin "1") (pinfunction "1_1") (pintype "input"))
    )
    (net (code "14") (name "Net-(D1-A)") (class "Default")
      (node (ref "D1") (pin "2") (pinfunction "A_2") (pintype "input"))
      (node (ref "L1") (pin "1") (pinfunction "1_1") (pintype "input"))
      (node (ref "U3") (pin "1") (pinfunction "SW_1") (pintype "input"))
    )
    (net (code "15") (name "Net-(D1_L1-A)") (class "Default")
      (node (ref "D1_L1") (pin "2") (pinfunction "A_2") (pintype "input"))
      (node (ref "Q1_L1") (pin "1") (pinfunction "G_1") (pintype "input"))
      (node (ref "R1_L1") (pin "2") (pinfunction "2_2") (pintype "input"))
    )
    (net (code "16") (name "Net-(D1_L1-C)") (class "Default")
      (node (ref "D1_L1") (pin "1") (pinfunction "C_1") (pintype "input"))
      (node (ref "R1_L1") (pin "1") (pinfunction "1_1") (pintype "input"))
      (node (ref "U1_L1") (pin "7") (pinfunction "HO_7") (pintype "input"))
    )
    (net (code "17") (name "Net-(D1_L2-A)") (class "Default")
      (node (ref "D1_L2") (pin "2") (pinfunction "A_2") (pintype "input"))
      (node (ref "Q1_L2") (pin "1") (pinfunction "G_1") (pintype "input"))
      (node (ref "R1_L2") (pin "2") (pinfunction "2_2") (pintype "input"))
    )
    (net (code "18") (name "Net-(D1_L2-C)") (class "Default")
      (node (ref "D1_L2") (pin "1") (pinfunction "C_1") (pintype "input"))
      (node (ref "R1_L2") (pin "1") (pinfunction "1_1") (pintype "input"))
      (node (ref "U1_L2") (pin "7") (pinfunction "HO_7") (pintype "input"))
    )
    (net (code "19") (name "Net-(D1_R1-A)") (class "Default")
      (node (ref "D1_R1") (pin "2") (pinfunction "A_2") (pintype "input"))
      (node (ref "Q1_R1") (pin "1") (pinfunction "G_1") (pintype "input"))
      (node (ref "R1_R1") (pin "2") (pinfunction "2_2") (pintype "input"))
    )
    (net (code "20") (name "Net-(D1_R1-C)") (class "Default")
      (node (ref "D1_R1") (pin "1") (pinfunction "C_1") (pintype "input"))
      (node (ref "R1_R1") (pin "1") (pinfunction "1_1") (pintype "input"))
      (node (ref "U1_R1") (pin "7") (pinfunction "HO_7") (pintype "input"))
    )
    (net (code "21") (name "Net-(D1_R2-A)") (class "Default")
      (node (ref "D1_R2") (pin "2") (pinfunction "A_2") (pintype "input"))
      (node (ref "Q1_R2") (pin "1") (pinfunction "G_1") (pintype "input"))
      (node (ref "R1_R2") (pin "2") (pinfunction "2_2") (pintype "input"))
    )
    (net (code "22") (name "Net-(D1_R2-C)") (class "Default")
      (node (ref "D1_R2") (pin "1") (pinfunction "C_1") (pintype "input"))
      (node (ref "R1_R2") (pin "1") (pinfunction "1_1") (pintype "input"))
      (node (ref "U1_R2") (pin "7") (pinfunction "HO_7") (pintype "input"))
    )
    (net (code "23") (name "Net-(D2_L1-A)") (class "Default")
      (node (ref "D2_L1") (pin "2") (pinfunction "A_2") (pintype "input"))
      (node (ref "Q2_L1") (pin "1") (pinfunction "G_1") (pintype "input"))
      (node (ref "R2_L1") (pin "2") (pinfunction "2_2") (pintype "input"))
    )
    (net (code "24") (name "Net-(D2_L1-C)") (class "Default")
      (node (ref "D2_L1") (pin "1") (pinfunction "C_1") (pintype "input"))
      (node (ref "R2_L1") (pin "1") (pinfunction "1_1") (pintype "input"))
      (node (ref "U1_L1") (pin "5") (pinfunction "LO_5") (pintype "input"))
    )
    (net (code "25") (name "Net-(D2_L2-A)") (class "Default")
      (node (ref "D2_L2") (pin "2") (pinfunction "A_2") (pintype "input"))
      (node (ref "Q2_L2") (pin "1") (pinfunction "G_1") (pintype "input"))
      (node (ref "R2_L2") (pin "2") (pinfunction "2_2") (pintype "input"))
    )
    (net (code "26") (name "Net-(D2_L2-C)") (class "Default")
      (node (ref "D2_L2") (pin "1") (pinfunction "C_1") (pintype "input"))
      (node (ref "R2_L2") (pin "1") (pinfunction "1_1") (pintype "input"))
      (node (ref "U1_L2") (pin "5") (pinfunction "LO_5") (pintype "input"))
    )
    (net (code "27") (name "Net-(D2_R1-A)") (class "Default")
      (node (ref "D2_R1") (pin "2") (pinfunction "A_2") (pintype "input"))
      (node (ref "Q2_R1") (pin "1") (pinfunction "G_1") (pintype "input"))
      (node (ref "R2_R1") (pin "2") (pinfunction "2_2") (pintype "input"))
    )
    (net (code "28") (name "Net-(D2_R1-C)") (class "Default")
      (node (ref "D2_R1") (pin "1") (pinfunction "C_1") (pintype "input"))
      (node (ref "R2_R1") (pin "1") (pinfunction "1_1") (pintype "input"))
      (node (ref "U1_R1") (pin "5") (pinfunction "LO_5") (pintype "input"))
    )
    (net (code "29") (name "Net-(D2_R2-A)") (class "Default")
      (node (ref "D2_R2") (pin "2") (pinfunction "A_2") (pintype "input"))
      (node (ref "Q2_R2") (pin "1") (pinfunction "G_1") (pintype "input"))
      (node (ref "R2_R2") (pin "2") (pinfunction "2_2") (pintype "input"))
    )
    (net (code "30") (name "Net-(D2_R2-C)") (class "Default")
      (node (ref "D2_R2") (pin "1") (pinfunction "C_1") (pintype "input"))
      (node (ref "R2_R2") (pin "1") (pinfunction "1_1") (pintype "input"))
      (node (ref "U1_R2") (pin "5") (pinfunction "LO_5") (pintype "input"))
    )
    (net (code "31") (name "Net-(D5_L1-K)") (class "Default")
      (node (ref "C2_L1") (pin "1") (pinfunction "1_1") (pintype "input"))
      (node (ref "D5_L1") (pin "1") (pinfunction "K_1") (pintype "input"))
      (node (ref "U1_L1") (pin "8") (pinfunction "VB_8") (pintype "input"))
    )
    (net (code "32") (name "Net-(D5_L2-K)") (class "Default")
      (node (ref "C2_L2") (pin "1") (pinfunction "1_1") (pintype "input"))
      (node (ref "D5_L2") (pin "1") (pinfunction "K_1") (pintype "input"))
      (node (ref "U1_L2") (pin "8") (pinfunction "VB_8") (pintype "input"))
    )
    (net (code "33") (name "Net-(D5_R1-K)") (class "Default")
      (node (ref "C2_R1") (pin "1") (pinfunction "1_1") (pintype "input"))
      (node (ref "D5_R1") (pin "1") (pinfunction "K_1") (pintype "input"))
      (node (ref "U1_R1") (pin "8") (pinfunction "VB_8") (pintype "input"))
    )
    (net (code "34") (name "Net-(D5_R2-K)") (class "Default")
      (node (ref "C2_R2") (pin "1") (pinfunction "1_1") (pintype "input"))
      (node (ref "D5_R2") (pin "1") (pinfunction "K_1") (pintype "input"))
      (node (ref "U1_R2") (pin "8") (pinfunction "VB_8") (pintype "input"))
    )
    (net (code "35") (name "Net-(LED1-A)") (class "Default")
      (node (ref "LED1") (pin "2") (pinfunction "A_2") (pintype "input"))
      (node (ref "R2") (pin "2") (pinfunction "2_2") (pintype "input"))
    )
    (net (code "36") (name "Net-(LED2-A)") (class "Default")
      (node (ref "LED2") (pin "2") (pinfunction "A_2") (pintype "input"))
      (node (ref "R3") (pin "1") (pinfunction "1_1") (pintype "input"))
    )
    (net (code "37") (name "Net-(LED3-A)") (class "Default")
      (node (ref "LED3") (pin "2") (pinfunction "A_2") (pintype "input"))
      (node (ref "R11") (pin "2") (pinfunction "2_2") (pintype "input"))
    )
    (net (code "38") (name "Net-(R4-Pad2)") (class "Default")
      (node (ref "R4") (pin "2") (pinfunction "2_2") (pintype "input"))
      (node (ref "R6") (pin "2") (pinfunction "2_2") (pintype "input"))
    )
    (net (code "39") (name "Net-(U3-FB)") (class "Default")
      (node (ref "R5") (pin "1") (pinfunction "1_1") (pintype "input"))
      (node (ref "R6") (pin "1") (pinfunction "1_1") (pintype "input"))
      (node (ref "U3") (pin "3") (pinfunction "FB_3") (pintype "input"))
    )
    (net (code "40") (name "Net-(U4-A1)") (class "Default")
      (node (ref "H1") (pin "5") (pinfunction "5_5") (pintype "input"))
      (node (ref "U4") (pin "2") (pinfunction "A1_2") (pintype "input"))
    )
    (net (code "41") (name "Net-(U4-A2)") (class "Default")
      (node (ref "H1") (pin "4") (pinfunction "4_4") (pintype "input"))
      (node (ref "U4") (pin "3") (pinfunction "A2_3") (pintype "input"))
    )
    (net (code "42") (name "Net-(U4-A3)") (class "Default")
      (node (ref "H1") (pin "3") (pinfunction "3_3") (pintype "input"))
      (node (ref "U4") (pin "4") (pinfunction "A3_4") (pintype "input"))
    )
    (net (code "43") (name "Net-(U4-A4)") (class "Default")
      (node (ref "H1") (pin "2") (pinfunction "2_2") (pintype "input"))
      (node (ref "U4") (pin "5") (pinfunction "A4_5") (pintype "input"))
    )
    (net (code "44") (name "PGND") (class "Default")
      (node (ref "C13") (pin "2") (pinfunction "2_2") (pintype "input"))
      (node (ref "CN1") (pin "1") (pinfunction "-_1") (pintype "input"))
      (node (ref "D4_L1") (pin "2") (pinfunction "A_2") (pintype "input"))
      (node (ref "D4_L2") (pin "2") (pinfunction "A_2") (pintype "input"))
      (node (ref "D4_R1") (pin "2") (pinfunction "A_2") (pintype "input"))
      (node (ref "D4_R2") (pin "2") (pinfunction "A_2") (pintype "input"))
      (node (ref "Q2_L1") (pin "3") (pinfunction "S_3") (pintype "input"))
      (node (ref "Q2_L2") (pin "3") (pinfunction "S_3") (pintype "input"))
      (node (ref "Q2_R1") (pin "3") (pinfunction "S_3") (pintype "input"))
      (node (ref "Q2_R2") (pin "3") (pinfunction "S_3") (pintype "input"))
      (node (ref "R12") (pin "1") (pinfunction "1_1") (pintype "input"))
    )
    (net (code "45") (name "VBAT") (class "Default")
      (node (ref "C1") (pin "2") (pinfunction "2_2") (pintype "input"))
      (node (ref "C10") (pin "2") (pinfunction "2_2") (pintype "input"))
      (node (ref "C2") (pin "2") (pinfunction "2_2") (pintype "input"))
      (node (ref "C9") (pin "2") (pinfunction "2_2") (pintype "input"))
      (node (ref "D3_L1") (pin "1") (pinfunction "C_1") (pintype "input"))
      (node (ref "D3_L2") (pin "1") (pinfunction "C_1") (pintype "input"))
      (node (ref "D3_R1") (pin "1") (pinfunction "C_1") (pintype "input"))
      (node (ref "D3_R2") (pin "1") (pinfunction "C_1") (pintype "input"))
      (node (ref "L1") (pin "2") (pinfunction "2_2") (pintype "input"))
      (node (ref "Q1_L1") (pin "2") (pinfunction "D_2") (pintype "input"))
      (node (ref "Q1_L2") (pin "2") (pinfunction "D_2") (pintype "input"))
      (node (ref "Q1_R1") (pin "2") (pinfunction "D_2") (pintype "input"))
      (node (ref "Q1_R2") (pin "2") (pinfunction "D_2") (pintype "input"))
      (node (ref "U2") (pin "3") (pinfunction "VIN_3") (pintype "input"))
      (node (ref "U3") (pin "4") (pinfunction "EN_4") (pintype "input"))
      (node (ref "U3") (pin "5") (pinfunction "VIN_5") (pintype "input"))
      (node (ref "U5") (pin "2") (pinfunction "2_2") (pintype "input"))
    )
    (net (code "46") (name "unconnected-(U1-VOUT(TAB)-Pad2)") (class "Default")
      (node (ref "U1") (pin "2") (pinfunction "VOUT(TAB)_2") (pintype "input+no_connect"))
    )
    (net (code "47") (name "unconnected-(U2-VOUT(TAB)-Pad2)") (class "Default")
      (node (ref "U2") (pin "2") (pinfunction "VOUT(TAB)_2") (pintype "input+no_connect"))
    )
    (net (code "48") (name "unconnected-(U3-NC-Pad6)") (class "Default")
      (node (ref "U3") (pin "6") (pinfunction "NC_6") (pintype "input+no_connect"))
    )
    (net (code "49") (name "unconnected-(U5-Pad3)") (class "Default")
      (node (ref "U5") (pin "3") (pinfunction "3_3") (pintype "input+no_connect"))
    )
  )
)
